# blink.net
KiCad netlist of a schematic drawn in EAGLE
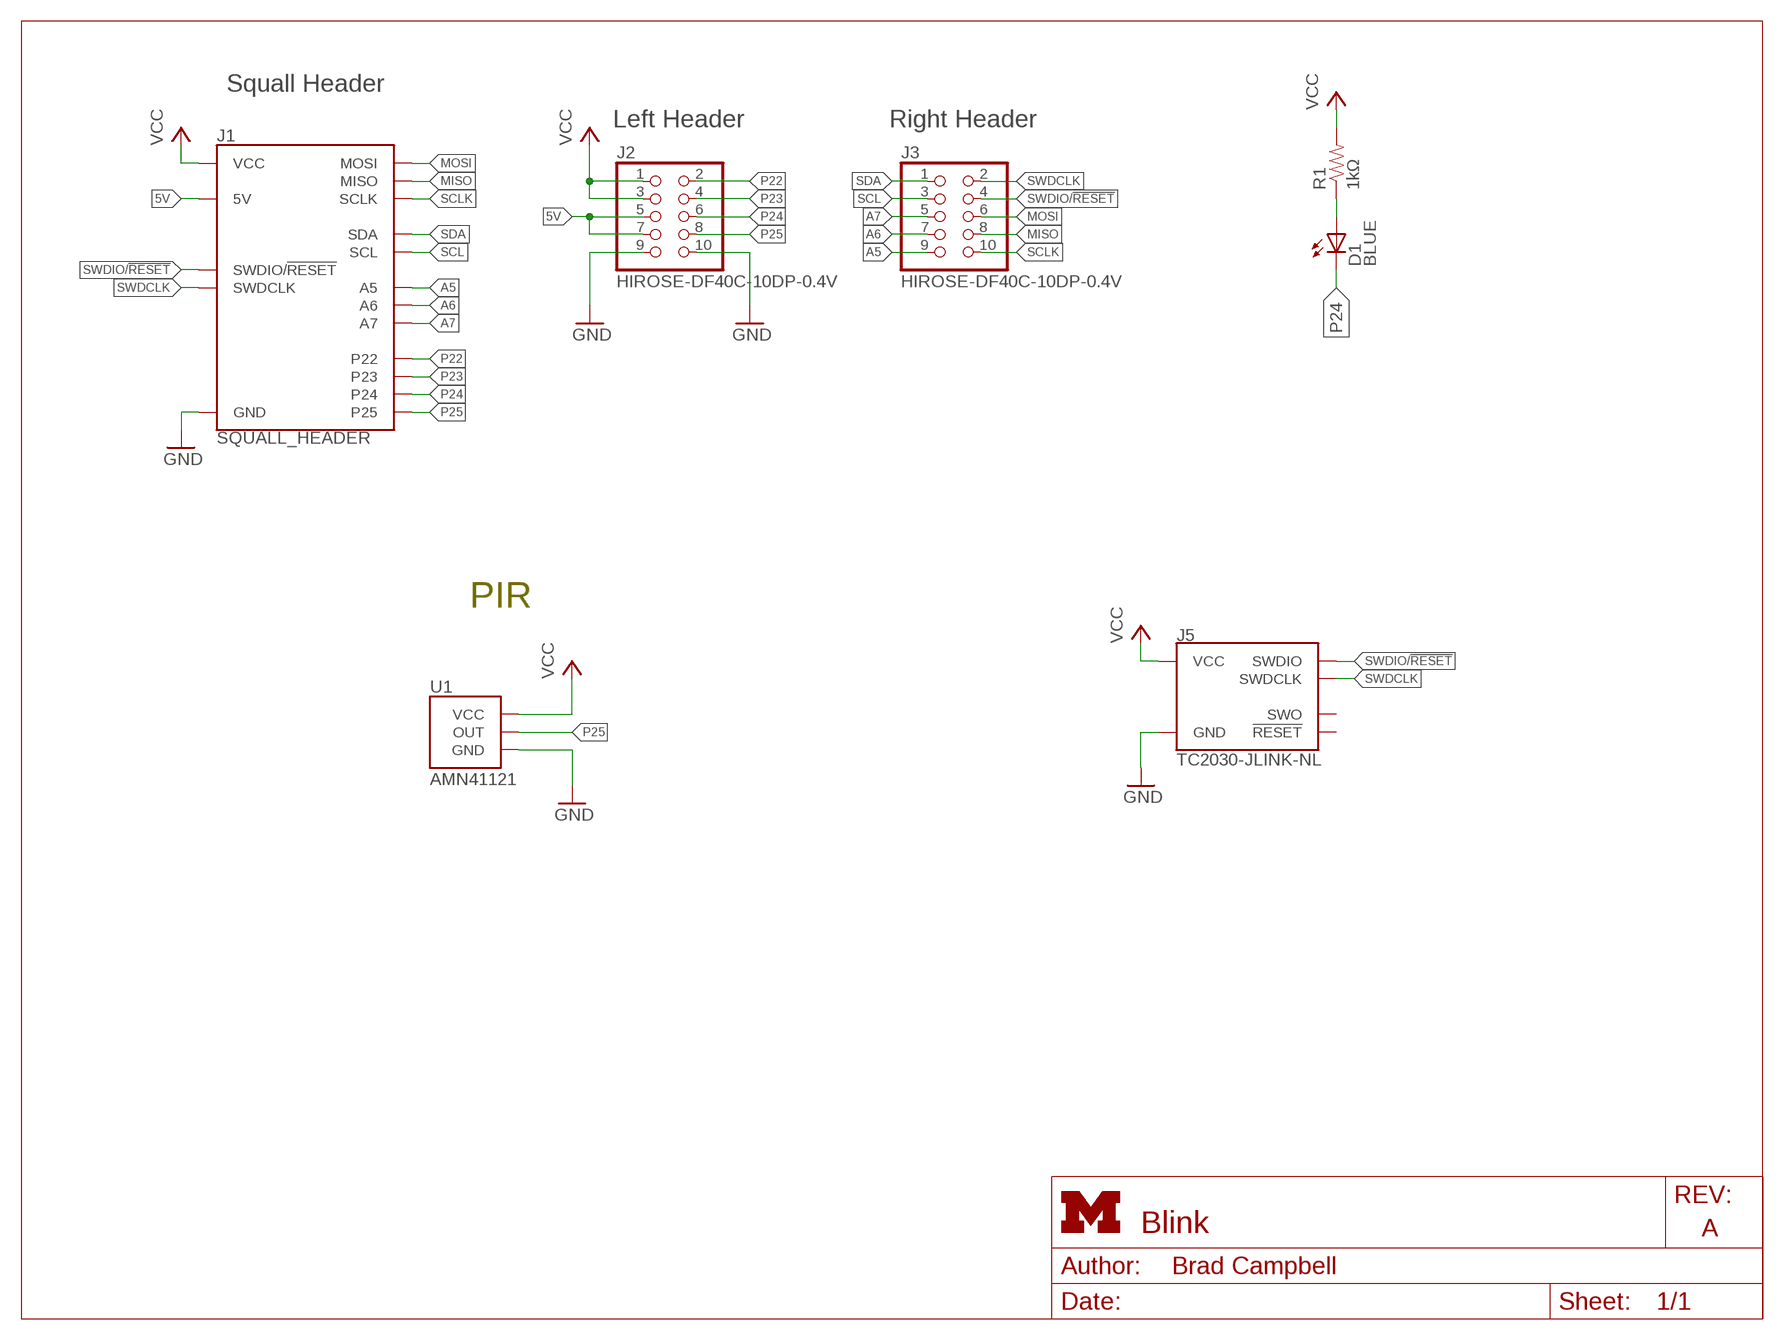
[diagram p0: schematic, sheet 1]

(export (version "E")
  (design (tool "Eeschema 10.0.6"))
  (components
    (comp (ref "D1")
      (value "BLUE")
      (footprint "eagle-import:LED-0603")
      (libsource (lib "eagle-import") (part "LED0603"))
    )
    (comp (ref "J1")
      (value "SQUALL_HEADER")
      (footprint "eagle-import:SQUALL_HEADER")
      (libsource (lib "eagle-import") (part "SQUALL_HEADER"))
    )
    (comp (ref "J2")
      (value "HIROSE-DF40C-10DP-0.4V")
      (footprint "eagle-import:2X5_SMD_0.4MM")
      (libsource (lib "eagle-import") (part "HIROSE-DF40C-10DP-0.4V"))
    )
    (comp (ref "J3")
      (value "HIROSE-DF40C-10DP-0.4V")
      (footprint "eagle-import:2X5_SMD_0.4MM")
      (libsource (lib "eagle-import") (part "HIROSE-DF40C-10DP-0.4V"))
    )
    (comp (ref "J5")
      (value "TC2030-JLINK-NL")
      (footprint "eagle-import:TC2030-IDC-NL")
      (libsource (lib "eagle-import") (part "TC2030-JLINK-NL"))
    )
    (comp (ref "R1")
      (value "1kΩ")
      (footprint "eagle-import:0402_RES")
      (libsource (lib "eagle-import") (part "RESISTOR0402_RES"))
    )
    (comp (ref "U1")
      (value "AMN41121")
      (footprint "eagle-import:AMN2")
      (fields (field (name "DIGIKEY") "255-3065-ND"))
      (libsource (lib "eagle-import") (part "AMN41121"))
    )
  )
  (nets
    (net (code "1") (name "/SWDIO{slash}~{RESET}") (class "Default")
      (node (ref "J1") (pin "B4") (pinfunction "SWDIO/~{RESET}_B4") (pintype "bidirectional"))
      (node (ref "J3") (pin "4") (pinfunction "4_4") (pintype "passive"))
      (node (ref "J5") (pin "2") (pinfunction "SWDIO_2") (pintype "bidirectional"))
    )
    (net (code "2") (name "5V") (class "Default")
      (node (ref "J1") (pin "A5") (pinfunction "5V_A5") (pintype "bidirectional"))
      (node (ref "J1") (pin "A7") (pinfunction "5V_A7") (pintype "bidirectional"))
      (node (ref "J2") (pin "5") (pinfunction "5_5") (pintype "passive"))
      (node (ref "J2") (pin "7") (pinfunction "7_7") (pintype "passive"))
    )
    (net (code "3") (name "A5") (class "Default")
      (node (ref "J1") (pin "B9") (pinfunction "A5_B9") (pintype "bidirectional"))
      (node (ref "J3") (pin "9") (pinfunction "9_9") (pintype "passive"))
    )
    (net (code "4") (name "A6") (class "Default")
      (node (ref "J1") (pin "B7") (pinfunction "A6_B7") (pintype "bidirectional"))
      (node (ref "J3") (pin "7") (pinfunction "7_7") (pintype "passive"))
    )
    (net (code "5") (name "A7") (class "Default")
      (node (ref "J1") (pin "B5") (pinfunction "A7_B5") (pintype "bidirectional"))
      (node (ref "J3") (pin "5") (pinfunction "5_5") (pintype "passive"))
    )
    (net (code "6") (name "GND") (class "Default")
      (node (ref "J1") (pin "A10") (pinfunction "GND_A10") (pintype "bidirectional"))
      (node (ref "J1") (pin "A9") (pinfunction "GND_A9") (pintype "bidirectional"))
      (node (ref "J2") (pin "10") (pinfunction "10_10") (pintype "passive"))
      (node (ref "J2") (pin "9") (pinfunction "9_9") (pintype "passive"))
      (node (ref "J5") (pin "5") (pinfunction "GND_5") (pintype "bidirectional"))
      (node (ref "U1") (pin "GND") (pinfunction "GND_GND") (pintype "bidirectional"))
    )
    (net (code "7") (name "MISO") (class "Default")
      (node (ref "J1") (pin "B8") (pinfunction "MISO_B8") (pintype "bidirectional"))
      (node (ref "J3") (pin "8") (pinfunction "8_8") (pintype "passive"))
    )
    (net (code "8") (name "MOSI") (class "Default")
      (node (ref "J1") (pin "B6") (pinfunction "MOSI_B6") (pintype "bidirectional"))
      (node (ref "J3") (pin "6") (pinfunction "6_6") (pintype "passive"))
    )
    (net (code "9") (name "Net-(D1-PadA)") (class "Default")
      (node (ref "D1") (pin "A") (pinfunction "A_A") (pintype "passive"))
      (node (ref "R1") (pin "1") (pinfunction "1_1") (pintype "passive"))
    )
    (net (code "10") (name "P22") (class "Default")
      (node (ref "J1") (pin "A2") (pinfunction "P22_A2") (pintype "bidirectional"))
      (node (ref "J2") (pin "2") (pinfunction "2_2") (pintype "passive"))
    )
    (net (code "11") (name "P23") (class "Default")
      (node (ref "J1") (pin "A4") (pinfunction "P23_A4") (pintype "bidirectional"))
      (node (ref "J2") (pin "4") (pinfunction "4_4") (pintype "passive"))
    )
    (net (code "12") (name "P24") (class "Default")
      (node (ref "D1") (pin "C") (pinfunction "C_C") (pintype "passive"))
      (node (ref "J1") (pin "A6") (pinfunction "P24_A6") (pintype "bidirectional"))
      (node (ref "J2") (pin "6") (pinfunction "6_6") (pintype "passive"))
    )
    (net (code "13") (name "P25") (class "Default")
      (node (ref "J1") (pin "A8") (pinfunction "P25_A8") (pintype "bidirectional"))
      (node (ref "J2") (pin "8") (pinfunction "8_8") (pintype "passive"))
      (node (ref "U1") (pin "OUT") (pinfunction "OUT_OUT") (pintype "bidirectional"))
    )
    (net (code "14") (name "SCL") (class "Default")
      (node (ref "J1") (pin "B3") (pinfunction "SCL_B3") (pintype "bidirectional"))
      (node (ref "J3") (pin "3") (pinfunction "3_3") (pintype "passive"))
    )
    (net (code "15") (name "SCLK") (class "Default")
      (node (ref "J1") (pin "B10") (pinfunction "SCLK_B10") (pintype "bidirectional"))
      (node (ref "J3") (pin "10") (pinfunction "10_10") (pintype "passive"))
    )
    (net (code "16") (name "SDA") (class "Default")
      (node (ref "J1") (pin "B1") (pinfunction "SDA_B1") (pintype "bidirectional"))
      (node (ref "J3") (pin "1") (pinfunction "1_1") (pintype "passive"))
    )
    (net (code "17") (name "SWDCLK") (class "Default")
      (node (ref "J1") (pin "B2") (pinfunction "SWDCLK_B2") (pintype "bidirectional"))
      (node (ref "J3") (pin "2") (pinfunction "2_2") (pintype "passive"))
      (node (ref "J5") (pin "4") (pinfunction "SWDCLK_4") (pintype "bidirectional"))
    )
    (net (code "18") (name "VCC") (class "Default")
      (node (ref "J1") (pin "A1") (pinfunction "VCC_A1") (pintype "bidirectional"))
      (node (ref "J1") (pin "A3") (pinfunction "VCC_A3") (pintype "bidirectional"))
      (node (ref "J2") (pin "1") (pinfunction "1_1") (pintype "passive"))
      (node (ref "J2") (pin "3") (pinfunction "3_3") (pintype "passive"))
      (node (ref "J5") (pin "1") (pinfunction "VCC_1") (pintype "bidirectional"))
      (node (ref "R1") (pin "2") (pinfunction "2_2") (pintype "passive"))
      (node (ref "U1") (pin "VCC") (pinfunction "VCC_VCC") (pintype "bidirectional"))
    )
    (net (code "19") (name "unconnected-(J5-SWO-Pad6)") (class "Default")
      (node (ref "J5") (pin "6") (pinfunction "SWO_6") (pintype "bidirectional"))
    )
    (net (code "20") (name "unconnected-(J5-~{RESET}-Pad3)") (class "Default")
      (node (ref "J5") (pin "3") (pinfunction "~{RESET}_3") (pintype "bidirectional"))
    )
  )
)
